# realtalker.net
KiCad netlist of a schematic drawn in EAGLE
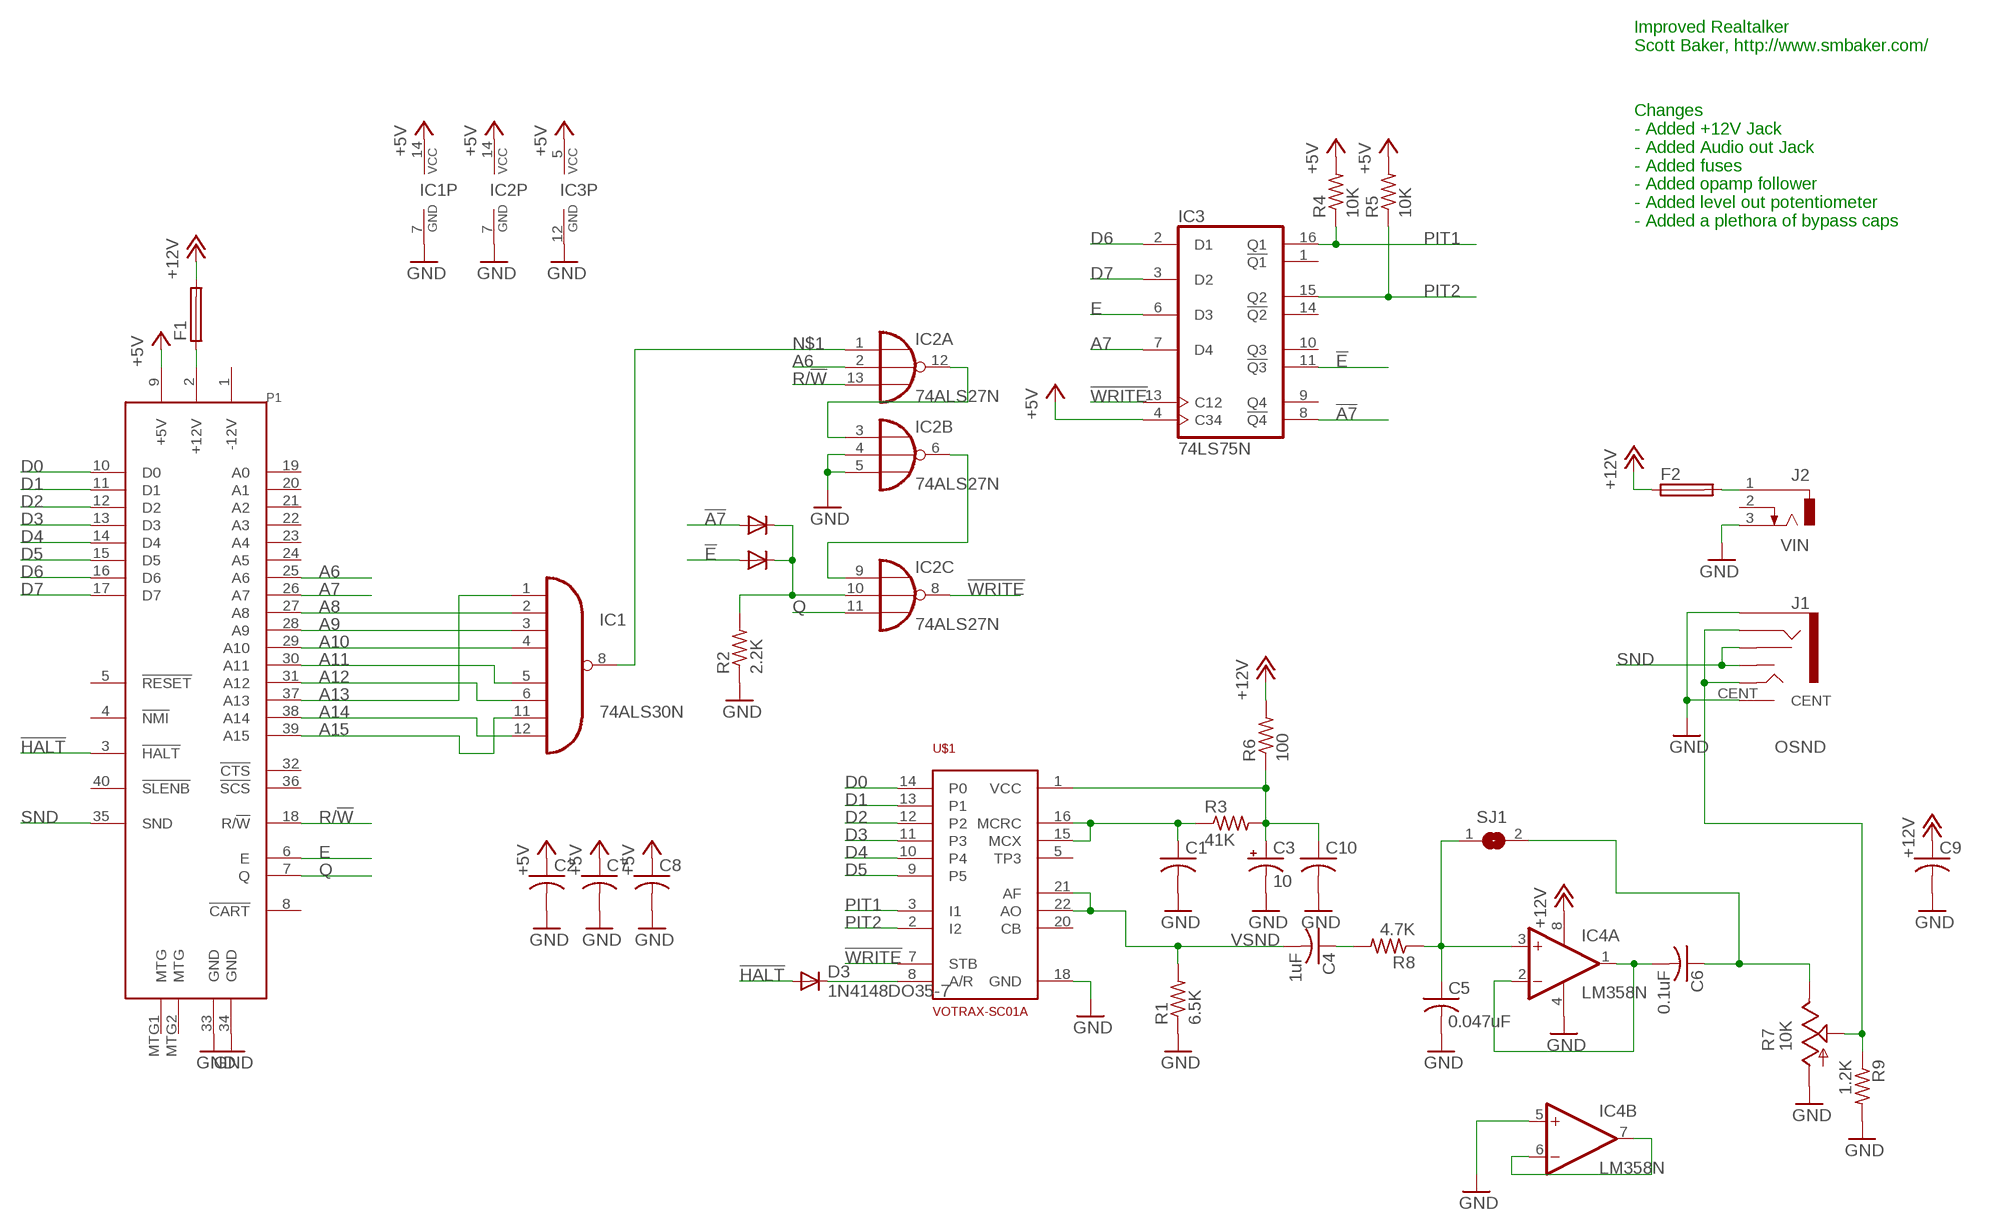
[diagram p0: schematic, sheet 1]

(export (version "E")
  (design (tool "Eeschema 10.0.6"))
  (components
    (comp (ref "C1")
      (value "C-US025-025X050")
      (footprint "eagle-import:C025-025X050")
      (libsource (lib "eagle-import") (part "C-US025-025X050"))
    )
    (comp (ref "C2")
      (value "C-US025-025X050")
      (footprint "eagle-import:C025-025X050")
      (libsource (lib "eagle-import") (part "C-US025-025X050"))
    )
    (comp (ref "C3")
      (value "10")
      (footprint "eagle-import:E2,5-6")
      (libsource (lib "eagle-import") (part "CPOL-USE2.5-6"))
    )
    (comp (ref "C4")
      (value "1uF")
      (footprint "eagle-import:C025-025X050")
      (libsource (lib "eagle-import") (part "C-US025-025X050"))
    )
    (comp (ref "C5")
      (value "0.047uF")
      (footprint "eagle-import:C025-025X050")
      (libsource (lib "eagle-import") (part "C-US025-025X050"))
    )
    (comp (ref "C6")
      (value "0.1uF")
      (footprint "eagle-import:C025-025X050")
      (libsource (lib "eagle-import") (part "C-US025-025X050"))
    )
    (comp (ref "C7")
      (value "C-US025-025X050")
      (footprint "eagle-import:C025-025X050")
      (libsource (lib "eagle-import") (part "C-US025-025X050"))
    )
    (comp (ref "C8")
      (value "C-US025-025X050")
      (footprint "eagle-import:C025-025X050")
      (libsource (lib "eagle-import") (part "C-US025-025X050"))
    )
    (comp (ref "C9")
      (value "C-US025-025X050")
      (footprint "eagle-import:C025-025X050")
      (libsource (lib "eagle-import") (part "C-US025-025X050"))
    )
    (comp (ref "C10")
      (value "C-US025-025X050")
      (footprint "eagle-import:C025-025X050")
      (libsource (lib "eagle-import") (part "C-US025-025X050"))
    )
    (comp (ref "D1")
      (value "1N4148DO35-7")
      (footprint "eagle-import:DO35-7")
      (libsource (lib "eagle-import") (part "1N4148DO35-7"))
    )
    (comp (ref "D2")
      (value "1N4148DO35-7")
      (footprint "eagle-import:DO35-7")
      (libsource (lib "eagle-import") (part "1N4148DO35-7"))
    )
    (comp (ref "D3")
      (value "1N4148DO35-7")
      (footprint "eagle-import:DO35-7")
      (libsource (lib "eagle-import") (part "1N4148DO35-7"))
    )
    (comp (ref "F1")
      (value "PTC_FUSE")
      (footprint "eagle-import:PTC_0.400")
      (libsource (lib "eagle-import") (part "PTC_FUSE"))
    )
    (comp (ref "F2")
      (value "PTC_FUSE")
      (footprint "eagle-import:PTC_0.400")
      (libsource (lib "eagle-import") (part "PTC_FUSE"))
    )
    (comp (ref "IC1")
      (value "74ALS30N")
      (footprint "eagle-import:DIL14")
      (libsource (lib "eagle-import") (part "7430NALS"))
    )
    (comp (ref "IC2")
      (value "74ALS27N")
      (footprint "eagle-import:DIL14")
      (libsource (lib "eagle-import") (part "7427NALS"))
    )
    (comp (ref "IC3")
      (value "74LS75N")
      (footprint "eagle-import:DIL16")
      (libsource (lib "eagle-import") (part "7475NLS"))
    )
    (comp (ref "IC4")
      (value "LM358N")
      (footprint "eagle-import:DIL08")
      (libsource (lib "eagle-import") (part "LM358N"))
    )
    (comp (ref "J1")
      (value "AUDIO_JACK_3.5MM")
      (footprint "eagle-import:AUDIO-JACK-G")
      (libsource (lib "eagle-import") (part "AUDIO_JACK_3.5MM"))
    )
    (comp (ref "J2")
      (value "VIN")
      (footprint "eagle-import:DCJACK")
      (libsource (lib "eagle-import") (part "DCJACK"))
    )
    (comp (ref "P1")
      (value "COCO-CARTMED")
      (footprint "eagle-import:COCO-CART_MEDIUM")
      (libsource (lib "eagle-import") (part "COCO-CARTMED"))
    )
    (comp (ref "R1")
      (value "6.5K")
      (footprint "eagle-import:0204_7")
      (libsource (lib "eagle-import") (part "R-US_0204/7"))
    )
    (comp (ref "R2")
      (value "2.2K")
      (footprint "eagle-import:0204_7")
      (libsource (lib "eagle-import") (part "R-US_0204/7"))
    )
    (comp (ref "R3")
      (value "41K")
      (footprint "eagle-import:0204_7")
      (libsource (lib "eagle-import") (part "R-US_0204/7"))
    )
    (comp (ref "R4")
      (value "10K")
      (footprint "eagle-import:0204_7")
      (libsource (lib "eagle-import") (part "R-US_0204/7"))
    )
    (comp (ref "R5")
      (value "10K")
      (footprint "eagle-import:0204_7")
      (libsource (lib "eagle-import") (part "R-US_0204/7"))
    )
    (comp (ref "R6")
      (value "100")
      (footprint "eagle-import:0204_7")
      (libsource (lib "eagle-import") (part "R-US_0204/7"))
    )
    (comp (ref "R7")
      (value "10K")
      (footprint "eagle-import:CT6")
      (libsource (lib "eagle-import") (part "TRIM_US-CT6"))
    )
    (comp (ref "R8")
      (value "4.7K")
      (footprint "eagle-import:0204_7")
      (libsource (lib "eagle-import") (part "R-US_0204/7"))
    )
    (comp (ref "R9")
      (value "1.2K")
      (footprint "eagle-import:0204_7")
      (libsource (lib "eagle-import") (part "R-US_0204/7"))
    )
    (comp (ref "SJ1") (value "SJ") (footprint "eagle-import:SJ") (libsource (lib "eagle-import") (part "SJ")))
    (comp (ref "U$1")
      (value "VOTRAX-SC01A")
      (footprint "eagle-import:DIL22-4")
      (libsource (lib "eagle-import") (part "VOTRAX-SC01A"))
    )
  )
  (nets
    (net (code "1") (name "+5V") (class "Default")
      (node (ref "C2") (pin "1") (pinfunction "1_1") (pintype "passive"))
      (node (ref "C7") (pin "1") (pinfunction "1_1") (pintype "passive"))
      (node (ref "C8") (pin "1") (pinfunction "1_1") (pintype "passive"))
      (node (ref "IC1") (pin "14") (pinfunction "VCC_14") (pintype "power_in"))
      (node (ref "IC2") (pin "14") (pinfunction "VCC_14") (pintype "power_in"))
      (node (ref "IC3") (pin "4") (pinfunction "C34_4") (pintype "input"))
      (node (ref "IC3") (pin "5") (pinfunction "VCC_5") (pintype "power_in"))
      (node (ref "P1") (pin "9") (pinfunction "+5V_9") (pintype "passive"))
      (node (ref "R4") (pin "2") (pinfunction "2_2") (pintype "passive"))
      (node (ref "R5") (pin "2") (pinfunction "2_2") (pintype "passive"))
    )
    (net (code "2") (name "+12V") (class "Default")
      (node (ref "C9") (pin "1") (pinfunction "1_1") (pintype "passive"))
      (node (ref "F1") (pin "2") (pinfunction "2_2") (pintype "passive"))
      (node (ref "F2") (pin "1") (pinfunction "1_1") (pintype "passive"))
      (node (ref "IC4") (pin "8") (pinfunction "V+_8") (pintype "power_in"))
      (node (ref "R6") (pin "2") (pinfunction "2_2") (pintype "passive"))
    )
    (net (code "3") (name "/A6") (class "Default")
      (node (ref "IC2") (pin "2") (pinfunction "I1_2") (pintype "input"))
      (node (ref "P1") (pin "25") (pinfunction "A6_25") (pintype "output"))
    )
    (net (code "4") (name "/A7") (class "Default")
      (node (ref "IC3") (pin "7") (pinfunction "D4_7") (pintype "input"))
      (node (ref "P1") (pin "26") (pinfunction "A7_26") (pintype "output"))
    )
    (net (code "5") (name "/A8") (class "Default")
      (node (ref "IC1") (pin "2") (pinfunction "I1_2") (pintype "input"))
      (node (ref "P1") (pin "27") (pinfunction "A8_27") (pintype "output"))
    )
    (net (code "6") (name "/A9") (class "Default")
      (node (ref "IC1") (pin "3") (pinfunction "I2_3") (pintype "input"))
      (node (ref "P1") (pin "28") (pinfunction "A9_28") (pintype "output"))
    )
    (net (code "7") (name "/A10") (class "Default")
      (node (ref "IC1") (pin "4") (pinfunction "I3_4") (pintype "input"))
      (node (ref "P1") (pin "29") (pinfunction "A10_29") (pintype "output"))
    )
    (net (code "8") (name "/A11") (class "Default")
      (node (ref "IC1") (pin "5") (pinfunction "I4_5") (pintype "input"))
      (node (ref "P1") (pin "30") (pinfunction "A11_30") (pintype "output"))
    )
    (net (code "9") (name "/A12") (class "Default")
      (node (ref "IC1") (pin "6") (pinfunction "I5_6") (pintype "input"))
      (node (ref "P1") (pin "31") (pinfunction "A12_31") (pintype "output"))
    )
    (net (code "10") (name "/A13") (class "Default")
      (node (ref "IC1") (pin "1") (pinfunction "I0_1") (pintype "input"))
      (node (ref "P1") (pin "37") (pinfunction "A13_37") (pintype "output"))
    )
    (net (code "11") (name "/A14") (class "Default")
      (node (ref "IC1") (pin "12") (pinfunction "I7_12") (pintype "input"))
      (node (ref "P1") (pin "38") (pinfunction "A14_38") (pintype "output"))
    )
    (net (code "12") (name "/A15") (class "Default")
      (node (ref "IC1") (pin "11") (pinfunction "I6_11") (pintype "input"))
      (node (ref "P1") (pin "39") (pinfunction "A15_39") (pintype "output"))
    )
    (net (code "13") (name "/D0") (class "Default")
      (node (ref "P1") (pin "10") (pinfunction "D0_10") (pintype "bidirectional"))
      (node (ref "U$1") (pin "14") (pinfunction "P0_14") (pintype "bidirectional"))
    )
    (net (code "14") (name "/D1") (class "Default")
      (node (ref "P1") (pin "11") (pinfunction "D1_11") (pintype "bidirectional"))
      (node (ref "U$1") (pin "13") (pinfunction "P1_13") (pintype "bidirectional"))
    )
    (net (code "15") (name "/D2") (class "Default")
      (node (ref "P1") (pin "12") (pinfunction "D2_12") (pintype "bidirectional"))
      (node (ref "U$1") (pin "12") (pinfunction "P2_12") (pintype "bidirectional"))
    )
    (net (code "16") (name "/D3") (class "Default")
      (node (ref "P1") (pin "13") (pinfunction "D3_13") (pintype "bidirectional"))
      (node (ref "U$1") (pin "11") (pinfunction "P3_11") (pintype "bidirectional"))
    )
    (net (code "17") (name "/D4") (class "Default")
      (node (ref "P1") (pin "14") (pinfunction "D4_14") (pintype "bidirectional"))
      (node (ref "U$1") (pin "10") (pinfunction "P4_10") (pintype "bidirectional"))
    )
    (net (code "18") (name "/D5") (class "Default")
      (node (ref "P1") (pin "15") (pinfunction "D5_15") (pintype "bidirectional"))
      (node (ref "U$1") (pin "9") (pinfunction "P5_9") (pintype "bidirectional"))
    )
    (net (code "19") (name "/D6") (class "Default")
      (node (ref "IC3") (pin "2") (pinfunction "D1_2") (pintype "input"))
      (node (ref "P1") (pin "16") (pinfunction "D6_16") (pintype "bidirectional"))
    )
    (net (code "20") (name "/D7") (class "Default")
      (node (ref "IC3") (pin "3") (pinfunction "D2_3") (pintype "input"))
      (node (ref "P1") (pin "17") (pinfunction "D7_17") (pintype "bidirectional"))
    )
    (net (code "21") (name "/E") (class "Default")
      (node (ref "IC3") (pin "6") (pinfunction "D3_6") (pintype "input"))
      (node (ref "P1") (pin "6") (pinfunction "E_6") (pintype "output"))
    )
    (net (code "22") (name "/N$1") (class "Default")
      (node (ref "IC1") (pin "8") (pinfunction "O_8") (pintype "output"))
      (node (ref "IC2") (pin "1") (pinfunction "I0_1") (pintype "input"))
    )
    (net (code "23") (name "/OSND") (class "Default")
      (node (ref "J1") (pin "RING") (pinfunction "RING_RING") (pintype "bidirectional"))
      (node (ref "J1") (pin "TIP") (pinfunction "TIP_TIP") (pintype "bidirectional"))
      (node (ref "R7") (pin "S") (pinfunction "S_S") (pintype "passive"))
      (node (ref "R9") (pin "1") (pinfunction "1_1") (pintype "passive"))
    )
    (net (code "24") (name "/PIT1") (class "Default")
      (node (ref "IC3") (pin "16") (pinfunction "Q1_16") (pintype "output"))
      (node (ref "R4") (pin "1") (pinfunction "1_1") (pintype "passive"))
      (node (ref "U$1") (pin "3") (pinfunction "I1_3") (pintype "bidirectional"))
    )
    (net (code "25") (name "/PIT2") (class "Default")
      (node (ref "IC3") (pin "15") (pinfunction "Q2_15") (pintype "output"))
      (node (ref "R5") (pin "1") (pinfunction "1_1") (pintype "passive"))
      (node (ref "U$1") (pin "2") (pinfunction "I2_2") (pintype "bidirectional"))
    )
    (net (code "26") (name "/Q") (class "Default")
      (node (ref "IC2") (pin "11") (pinfunction "I2_11") (pintype "input"))
      (node (ref "P1") (pin "7") (pinfunction "Q_7") (pintype "output"))
    )
    (net (code "27") (name "/R{slash}~{W}") (class "Default")
      (node (ref "IC2") (pin "13") (pinfunction "I2_13") (pintype "input"))
      (node (ref "P1") (pin "18") (pinfunction "R/~{W}_18") (pintype "output"))
    )
    (net (code "28") (name "/SND") (class "Default")
      (node (ref "J1") (pin "RSH") (pinfunction "RSH_RSH") (pintype "bidirectional"))
      (node (ref "J1") (pin "TSH") (pinfunction "TSH_TSH") (pintype "bidirectional"))
      (node (ref "P1") (pin "35") (pinfunction "SND_35") (pintype "bidirectional"))
    )
    (net (code "29") (name "/VSND") (class "Default")
      (node (ref "C4") (pin "2") (pinfunction "2_2") (pintype "passive"))
      (node (ref "R1") (pin "2") (pinfunction "2_2") (pintype "passive"))
      (node (ref "U$1") (pin "21") (pinfunction "AF_21") (pintype "bidirectional"))
      (node (ref "U$1") (pin "22") (pinfunction "AO_22") (pintype "bidirectional"))
    )
    (net (code "30") (name "/~{A7}") (class "Default")
      (node (ref "D2") (pin "A") (pinfunction "A_A") (pintype "passive"))
      (node (ref "IC3") (pin "8") (pinfunction "~{Q4}_8") (pintype "output"))
    )
    (net (code "31") (name "/~{E}") (class "Default")
      (node (ref "D1") (pin "A") (pinfunction "A_A") (pintype "passive"))
      (node (ref "IC3") (pin "11") (pinfunction "~{Q3}_11") (pintype "output"))
    )
    (net (code "32") (name "/~{HALT}") (class "Default")
      (node (ref "D3") (pin "A") (pinfunction "A_A") (pintype "passive"))
      (node (ref "P1") (pin "3") (pinfunction "~{HALT}_3") (pintype "bidirectional"))
    )
    (net (code "33") (name "/~{WRITE}") (class "Default")
      (node (ref "IC2") (pin "8") (pinfunction "O_8") (pintype "output"))
      (node (ref "IC3") (pin "13") (pinfunction "C12_13") (pintype "input"))
      (node (ref "U$1") (pin "7") (pinfunction "STB_7") (pintype "bidirectional"))
    )
    (net (code "34") (name "GND") (class "Default")
      (node (ref "C1") (pin "2") (pinfunction "2_2") (pintype "passive"))
      (node (ref "C10") (pin "2") (pinfunction "2_2") (pintype "passive"))
      (node (ref "C2") (pin "2") (pinfunction "2_2") (pintype "passive"))
      (node (ref "C3") (pin "-") (pinfunction "-_-") (pintype "passive"))
      (node (ref "C5") (pin "2") (pinfunction "2_2") (pintype "passive"))
      (node (ref "C7") (pin "2") (pinfunction "2_2") (pintype "passive"))
      (node (ref "C8") (pin "2") (pinfunction "2_2") (pintype "passive"))
      (node (ref "C9") (pin "2") (pinfunction "2_2") (pintype "passive"))
      (node (ref "IC1") (pin "7") (pinfunction "GND_7") (pintype "power_in"))
      (node (ref "IC2") (pin "4") (pinfunction "I1_4") (pintype "input"))
      (node (ref "IC2") (pin "5") (pinfunction "I2_5") (pintype "input"))
      (node (ref "IC2") (pin "7") (pinfunction "GND_7") (pintype "power_in"))
      (node (ref "IC3") (pin "12") (pinfunction "GND_12") (pintype "power_in"))
      (node (ref "IC4") (pin "4") (pinfunction "V-_4") (pintype "power_in"))
      (node (ref "IC4") (pin "5") (pinfunction "+IN_5") (pintype "input"))
      (node (ref "J1") (pin "CENT") (pinfunction "CENT_CENT") (pintype "bidirectional"))
      (node (ref "J1") (pin "SLEEVE") (pinfunction "SLEEVE_SLEEVE") (pintype "bidirectional"))
      (node (ref "J2") (pin "3") (pinfunction "3_3") (pintype "passive"))
      (node (ref "P1") (pin "33") (pinfunction "GND_33") (pintype "passive"))
      (node (ref "P1") (pin "34") (pinfunction "GND_34") (pintype "passive"))
      (node (ref "R1") (pin "1") (pinfunction "1_1") (pintype "passive"))
      (node (ref "R2") (pin "1") (pinfunction "1_1") (pintype "passive"))
      (node (ref "R7") (pin "A") (pinfunction "A_A") (pintype "passive"))
      (node (ref "R9") (pin "2") (pinfunction "2_2") (pintype "passive"))
      (node (ref "U$1") (pin "18") (pinfunction "GND_18") (pintype "bidirectional"))
    )
    (net (code "35") (name "Net-(C4-Pad1)") (class "Default")
      (node (ref "C4") (pin "1") (pinfunction "1_1") (pintype "passive"))
      (node (ref "R8") (pin "2") (pinfunction "2_2") (pintype "passive"))
    )
    (net (code "36") (name "Net-(C6-Pad1)") (class "Default")
      (node (ref "C6") (pin "1") (pinfunction "1_1") (pintype "passive"))
      (node (ref "R7") (pin "E") (pinfunction "E_E") (pintype "passive"))
      (node (ref "SJ1") (pin "2") (pinfunction "2_2") (pintype "passive"))
    )
    (net (code "37") (name "Net-(F2-Pad2)") (class "Default")
      (node (ref "F2") (pin "2") (pinfunction "2_2") (pintype "passive"))
      (node (ref "J2") (pin "1") (pinfunction "1_1") (pintype "passive"))
    )
    (net (code "38") (name "Net-(IC2A-O)") (class "Default")
      (node (ref "IC2") (pin "12") (pinfunction "O_12") (pintype "output"))
      (node (ref "IC2") (pin "3") (pinfunction "I0_3") (pintype "input"))
    )
    (net (code "39") (name "Net-(IC2B-O)") (class "Default")
      (node (ref "IC2") (pin "6") (pinfunction "O_6") (pintype "output"))
      (node (ref "IC2") (pin "9") (pinfunction "I0_9") (pintype "input"))
    )
    (net (code "40") (name "Net-(IC2C-I1)") (class "Default")
      (node (ref "D1") (pin "C") (pinfunction "C_C") (pintype "passive"))
      (node (ref "D2") (pin "C") (pinfunction "C_C") (pintype "passive"))
      (node (ref "IC2") (pin "10") (pinfunction "I1_10") (pintype "input"))
      (node (ref "R2") (pin "2") (pinfunction "2_2") (pintype "passive"))
    )
    (net (code "41") (name "Net-(IC4A-+IN)") (class "Default")
      (node (ref "C5") (pin "1") (pinfunction "1_1") (pintype "passive"))
      (node (ref "IC4") (pin "3") (pinfunction "+IN_3") (pintype "input"))
      (node (ref "R8") (pin "1") (pinfunction "1_1") (pintype "passive"))
      (node (ref "SJ1") (pin "1") (pinfunction "1_1") (pintype "passive"))
    )
    (net (code "42") (name "Net-(IC4A--IN)") (class "Default")
      (node (ref "C6") (pin "2") (pinfunction "2_2") (pintype "passive"))
      (node (ref "IC4") (pin "1") (pinfunction "OUT_1") (pintype "output"))
      (node (ref "IC4") (pin "2") (pinfunction "-IN_2") (pintype "input"))
    )
    (net (code "43") (name "Net-(IC4B--IN)") (class "Default")
      (node (ref "IC4") (pin "6") (pinfunction "-IN_6") (pintype "input"))
      (node (ref "IC4") (pin "7") (pinfunction "OUT_7") (pintype "output"))
    )
    (net (code "44") (name "Net-(P1-+12V)") (class "Default")
      (node (ref "F1") (pin "1") (pinfunction "1_1") (pintype "passive"))
      (node (ref "P1") (pin "2") (pinfunction "+12V_2") (pintype "passive"))
    )
    (net (code "45") (name "Net-(U$1-A{slash}R)") (class "Default")
      (node (ref "D3") (pin "C") (pinfunction "C_C") (pintype "passive"))
      (node (ref "U$1") (pin "8") (pinfunction "A/R_8") (pintype "bidirectional"))
    )
    (net (code "46") (name "Net-(U$1-MCRC)") (class "Default")
      (node (ref "C1") (pin "1") (pinfunction "1_1") (pintype "passive"))
      (node (ref "R3") (pin "1") (pinfunction "1_1") (pintype "passive"))
      (node (ref "U$1") (pin "15") (pinfunction "MCX_15") (pintype "bidirectional"))
      (node (ref "U$1") (pin "16") (pinfunction "MCRC_16") (pintype "bidirectional"))
    )
    (net (code "47") (name "Net-(U$1-VCC)") (class "Default")
      (node (ref "C10") (pin "1") (pinfunction "1_1") (pintype "passive"))
      (node (ref "C3") (pin "+") (pinfunction "+_+") (pintype "passive"))
      (node (ref "R3") (pin "2") (pinfunction "2_2") (pintype "passive"))
      (node (ref "R6") (pin "1") (pinfunction "1_1") (pintype "passive"))
      (node (ref "U$1") (pin "1") (pinfunction "VCC_1") (pintype "bidirectional"))
    )
    (net (code "48") (name "unconnected-(IC3A-Q3-Pad10)") (class "Default")
      (node (ref "IC3") (pin "10") (pinfunction "Q3_10") (pintype "output"))
    )
    (net (code "49") (name "unconnected-(IC3A-Q4-Pad9)") (class "Default")
      (node (ref "IC3") (pin "9") (pinfunction "Q4_9") (pintype "output"))
    )
    (net (code "50") (name "unconnected-(IC3A-~{Q1}-Pad1)") (class "Default")
      (node (ref "IC3") (pin "1") (pinfunction "~{Q1}_1") (pintype "output"))
    )
    (net (code "51") (name "unconnected-(IC3A-~{Q2}-Pad14)") (class "Default")
      (node (ref "IC3") (pin "14") (pinfunction "~{Q2}_14") (pintype "output"))
    )
    (net (code "52") (name "unconnected-(J2-Pad2)") (class "Default")
      (node (ref "J2") (pin "2") (pinfunction "2_2") (pintype "passive"))
    )
    (net (code "53") (name "unconnected-(P1--12V-Pad1)") (class "Default")
      (node (ref "P1") (pin "1") (pinfunction "-12V_1") (pintype "passive"))
    )
    (net (code "54") (name "unconnected-(P1-A0-Pad19)") (class "Default")
      (node (ref "P1") (pin "19") (pinfunction "A0_19") (pintype "output"))
    )
    (net (code "55") (name "unconnected-(P1-A1-Pad20)") (class "Default")
      (node (ref "P1") (pin "20") (pinfunction "A1_20") (pintype "output"))
    )
    (net (code "56") (name "unconnected-(P1-A2-Pad21)") (class "Default")
      (node (ref "P1") (pin "21") (pinfunction "A2_21") (pintype "output"))
    )
    (net (code "57") (name "unconnected-(P1-A3-Pad22)") (class "Default")
      (node (ref "P1") (pin "22") (pinfunction "A3_22") (pintype "output"))
    )
    (net (code "58") (name "unconnected-(P1-A4-Pad23)") (class "Default")
      (node (ref "P1") (pin "23") (pinfunction "A4_23") (pintype "output"))
    )
    (net (code "59") (name "unconnected-(P1-A5-Pad24)") (class "Default")
      (node (ref "P1") (pin "24") (pinfunction "A5_24") (pintype "output"))
    )
    (net (code "60") (name "unconnected-(P1-MTG-PadMTG1)") (class "Default")
      (node (ref "P1") (pin "MTG1") (pinfunction "MTG_MTG1") (pintype "passive"))
    )
    (net (code "61") (name "unconnected-(P1-MTG-PadMTG2)") (class "Default")
      (node (ref "P1") (pin "MTG2") (pinfunction "MTG_MTG2") (pintype "passive"))
    )
    (net (code "62") (name "unconnected-(P1-~{CART}-Pad8)") (class "Default")
      (node (ref "P1") (pin "8") (pinfunction "~{CART}_8") (pintype "input"))
    )
    (net (code "63") (name "unconnected-(P1-~{CTS}-Pad32)") (class "Default")
      (node (ref "P1") (pin "32") (pinfunction "~{CTS}_32") (pintype "output"))
    )
    (net (code "64") (name "unconnected-(P1-~{NMI}-Pad4)") (class "Default")
      (node (ref "P1") (pin "4") (pinfunction "~{NMI}_4") (pintype "bidirectional"))
    )
    (net (code "65") (name "unconnected-(P1-~{RESET}-Pad5)") (class "Default")
      (node (ref "P1") (pin "5") (pinfunction "~{RESET}_5") (pintype "bidirectional"))
    )
    (net (code "66") (name "unconnected-(P1-~{SCS}-Pad36)") (class "Default")
      (node (ref "P1") (pin "36") (pinfunction "~{SCS}_36") (pintype "output"))
    )
    (net (code "67") (name "unconnected-(P1-~{SLENB}-Pad40)") (class "Default")
      (node (ref "P1") (pin "40") (pinfunction "~{SLENB}_40") (pintype "input"))
    )
    (net (code "68") (name "unconnected-(U$1-CB-Pad20)") (class "Default")
      (node (ref "U$1") (pin "20") (pinfunction "CB_20") (pintype "bidirectional"))
    )
    (net (code "69") (name "unconnected-(U$1-TP3-Pad5)") (class "Default")
      (node (ref "U$1") (pin "5") (pinfunction "TP3_5") (pintype "bidirectional"))
    )
  )
)
